# shield.net
KiCad netlist of a schematic drawn in EAGLE
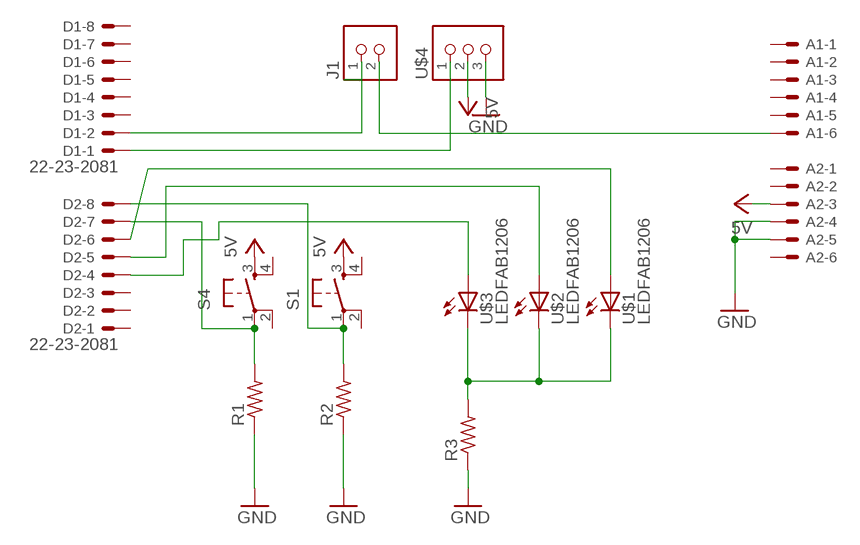
[diagram p0: schematic, sheet 2]

(export (version "E")
  (design (tool "Eeschema 10.0.6"))
  (components
    (comp (ref "A1")
      (value "22-23-2061")
      (footprint "eagle-import:22-23-2061")
      (fields (field (name "MF") "MOLEX"))
      (libsource (lib "eagle-import") (part "22-23-2061"))
    )
    (comp (ref "A2")
      (value "22-23-2061")
      (footprint "eagle-import:22-23-2061")
      (fields (field (name "MF") "MOLEX"))
      (libsource (lib "eagle-import") (part "22-23-2061"))
    )
    (comp (ref "D1")
      (value "22-23-2081")
      (footprint "eagle-import:22-23-2081")
      (fields (field (name "MF") "MOLEX"))
      (libsource (lib "eagle-import") (part "22-23-2081"))
    )
    (comp (ref "D2")
      (value "22-23-2081")
      (footprint "eagle-import:22-23-2081")
      (fields (field (name "MF") "MOLEX"))
      (libsource (lib "eagle-import") (part "22-23-2081"))
    )
    (comp (ref "J1")
      (value "TERM-1X02-FABLAB")
      (footprint "eagle-import:ED555DS-2DS")
      (libsource (lib "eagle-import") (part "TERM-1X02-FABLAB"))
    )
    (comp (ref "R1")
      (value "RES-US1206FAB")
      (footprint "eagle-import:R1206FAB")
      (libsource (lib "eagle-import") (part "RES-US1206FAB"))
    )
    (comp (ref "R2")
      (value "RES-US1206FAB")
      (footprint "eagle-import:R1206FAB")
      (libsource (lib "eagle-import") (part "RES-US1206FAB"))
    )
    (comp (ref "R3")
      (value "RES-US1206FAB")
      (footprint "eagle-import:R1206FAB")
      (libsource (lib "eagle-import") (part "RES-US1206FAB"))
    )
    (comp (ref "S1")
      (value "6MM_SWITCH6MM_SWITCH")
      (footprint "eagle-import:6MM_SWITCH")
      (libsource (lib "eagle-import") (part "6MM_SWITCH6MM_SWITCH"))
    )
    (comp (ref "S4")
      (value "6MM_SWITCH6MM_SWITCH")
      (footprint "eagle-import:6MM_SWITCH")
      (libsource (lib "eagle-import") (part "6MM_SWITCH6MM_SWITCH"))
    )
    (comp (ref "U$1")
      (value "LEDFAB1206")
      (footprint "eagle-import:LED1206FAB")
      (libsource (lib "eagle-import") (part "LEDFAB1206"))
    )
    (comp (ref "U$2")
      (value "LEDFAB1206")
      (footprint "eagle-import:LED1206FAB")
      (libsource (lib "eagle-import") (part "LEDFAB1206"))
    )
    (comp (ref "U$3")
      (value "LEDFAB1206")
      (footprint "eagle-import:LED1206FAB")
      (libsource (lib "eagle-import") (part "LEDFAB1206"))
    )
    (comp (ref "U$4")
      (value "TERM-1X03'-FABLAB'")
      (footprint "eagle-import:ED555DS-3DS")
      (libsource (lib "eagle-import") (part "TERM-1X03'-FABLAB'"))
    )
  )
  (nets
    (net (code "1") (name "GND") (class "Default")
      (node (ref "A2") (pin "4") (pinfunction "S_4") (pintype "passive"))
      (node (ref "A2") (pin "5") (pinfunction "S_5") (pintype "passive"))
      (node (ref "R1") (pin "1") (pinfunction "1_1") (pintype "passive"))
      (node (ref "R2") (pin "1") (pinfunction "1_1") (pintype "passive"))
      (node (ref "R3") (pin "1") (pinfunction "1_1") (pintype "passive"))
      (node (ref "U$4") (pin "3") (pinfunction "3_3") (pintype "passive"))
    )
    (net (code "2") (name "Net-(A1F-S)") (class "Default")
      (node (ref "A1") (pin "6") (pinfunction "S_6") (pintype "passive"))
      (node (ref "J1") (pin "2") (pinfunction "2_2") (pintype "passive"))
    )
    (net (code "3") (name "Net-(D1A-S)") (class "Default")
      (node (ref "D1") (pin "1") (pinfunction "S_1") (pintype "passive"))
      (node (ref "U$4") (pin "1") (pinfunction "1_1") (pintype "passive"))
    )
    (net (code "4") (name "Net-(D1B-S)") (class "Default")
      (node (ref "D1") (pin "2") (pinfunction "S_2") (pintype "passive"))
      (node (ref "J1") (pin "1") (pinfunction "1_1") (pintype "passive"))
    )
    (net (code "5") (name "Net-(D2D-S)") (class "Default")
      (node (ref "D2") (pin "4") (pinfunction "S_4") (pintype "passive"))
      (node (ref "U$3") (pin "1") (pinfunction "A_1") (pintype "passive"))
    )
    (net (code "6") (name "Net-(D2E-S)") (class "Default")
      (node (ref "D2") (pin "5") (pinfunction "S_5") (pintype "passive"))
      (node (ref "U$2") (pin "1") (pinfunction "A_1") (pintype "passive"))
    )
    (net (code "7") (name "Net-(D2F-S)") (class "Default")
      (node (ref "D2") (pin "6") (pinfunction "S_6") (pintype "passive"))
      (node (ref "U$1") (pin "1") (pinfunction "A_1") (pintype "passive"))
    )
    (net (code "8") (name "Net-(D2G-S)") (class "Default")
      (node (ref "D2") (pin "7") (pinfunction "S_7") (pintype "passive"))
      (node (ref "R1") (pin "2") (pinfunction "2_2") (pintype "passive"))
      (node (ref "S4") (pin "1") (pinfunction "P_1") (pintype "passive"))
    )
    (net (code "9") (name "Net-(D2H-S)") (class "Default")
      (node (ref "D2") (pin "8") (pinfunction "S_8") (pintype "passive"))
      (node (ref "R2") (pin "2") (pinfunction "2_2") (pintype "passive"))
      (node (ref "S1") (pin "1") (pinfunction "P_1") (pintype "passive"))
    )
    (net (code "10") (name "Net-(U$1-C)") (class "Default")
      (node (ref "R3") (pin "2") (pinfunction "2_2") (pintype "passive"))
      (node (ref "U$1") (pin "2") (pinfunction "C_2") (pintype "passive"))
      (node (ref "U$2") (pin "2") (pinfunction "C_2") (pintype "passive"))
      (node (ref "U$3") (pin "2") (pinfunction "C_2") (pintype "passive"))
    )
    (net (code "11") (name "VCC") (class "Default")
      (node (ref "A2") (pin "3") (pinfunction "S_3") (pintype "passive"))
      (node (ref "S1") (pin "3") (pinfunction "S_3") (pintype "passive"))
      (node (ref "S4") (pin "3") (pinfunction "S_3") (pintype "passive"))
      (node (ref "U$4") (pin "2") (pinfunction "2_2") (pintype "passive"))
    )
    (net (code "12") (name "unconnected-(A1A-S-Pad1)") (class "Default")
      (node (ref "A1") (pin "1") (pinfunction "S_1") (pintype "passive"))
    )
    (net (code "13") (name "unconnected-(A1B-S-Pad2)") (class "Default")
      (node (ref "A1") (pin "2") (pinfunction "S_2") (pintype "passive"))
    )
    (net (code "14") (name "unconnected-(A1C-S-Pad3)") (class "Default")
      (node (ref "A1") (pin "3") (pinfunction "S_3") (pintype "passive"))
    )
    (net (code "15") (name "unconnected-(A1D-S-Pad4)") (class "Default")
      (node (ref "A1") (pin "4") (pinfunction "S_4") (pintype "passive"))
    )
    (net (code "16") (name "unconnected-(A1E-S-Pad5)") (class "Default")
      (node (ref "A1") (pin "5") (pinfunction "S_5") (pintype "passive"))
    )
    (net (code "17") (name "unconnected-(A2A-S-Pad1)") (class "Default")
      (node (ref "A2") (pin "1") (pinfunction "S_1") (pintype "passive"))
    )
    (net (code "18") (name "unconnected-(A2B-S-Pad2)") (class "Default")
      (node (ref "A2") (pin "2") (pinfunction "S_2") (pintype "passive"))
    )
    (net (code "19") (name "unconnected-(A2F-S-Pad6)") (class "Default")
      (node (ref "A2") (pin "6") (pinfunction "S_6") (pintype "passive"))
    )
    (net (code "20") (name "unconnected-(D1C-S-Pad3)") (class "Default")
      (node (ref "D1") (pin "3") (pinfunction "S_3") (pintype "passive"))
    )
    (net (code "21") (name "unconnected-(D1D-S-Pad4)") (class "Default")
      (node (ref "D1") (pin "4") (pinfunction "S_4") (pintype "passive"))
    )
    (net (code "22") (name "unconnected-(D1E-S-Pad5)") (class "Default")
      (node (ref "D1") (pin "5") (pinfunction "S_5") (pintype "passive"))
    )
    (net (code "23") (name "unconnected-(D1F-S-Pad6)") (class "Default")
      (node (ref "D1") (pin "6") (pinfunction "S_6") (pintype "passive"))
    )
    (net (code "24") (name "unconnected-(D1G-S-Pad7)") (class "Default")
      (node (ref "D1") (pin "7") (pinfunction "S_7") (pintype "passive"))
    )
    (net (code "25") (name "unconnected-(D1H-S-Pad8)") (class "Default")
      (node (ref "D1") (pin "8") (pinfunction "S_8") (pintype "passive"))
    )
    (net (code "26") (name "unconnected-(D2A-S-Pad1)") (class "Default")
      (node (ref "D2") (pin "1") (pinfunction "S_1") (pintype "passive"))
    )
    (net (code "27") (name "unconnected-(D2B-S-Pad2)") (class "Default")
      (node (ref "D2") (pin "2") (pinfunction "S_2") (pintype "passive"))
    )
    (net (code "28") (name "unconnected-(D2C-S-Pad3)") (class "Default")
      (node (ref "D2") (pin "3") (pinfunction "S_3") (pintype "passive"))
    )
    (net (code "29") (name "unconnected-(S1-P1-Pad2)") (class "Default")
      (node (ref "S1") (pin "2") (pinfunction "P1_2") (pintype "passive"))
    )
    (net (code "30") (name "unconnected-(S1-S1-Pad4)") (class "Default")
      (node (ref "S1") (pin "4") (pinfunction "S1_4") (pintype "passive"))
    )
    (net (code "31") (name "unconnected-(S4-P1-Pad2)") (class "Default")
      (node (ref "S4") (pin "2") (pinfunction "P1_2") (pintype "passive"))
    )
    (net (code "32") (name "unconnected-(S4-S1-Pad4)") (class "Default")
      (node (ref "S4") (pin "4") (pinfunction "S1_4") (pintype "passive"))
    )
  )
)
